# Arduino_Electronic_Load.net
KiCad netlist of a schematic drawn in EAGLE
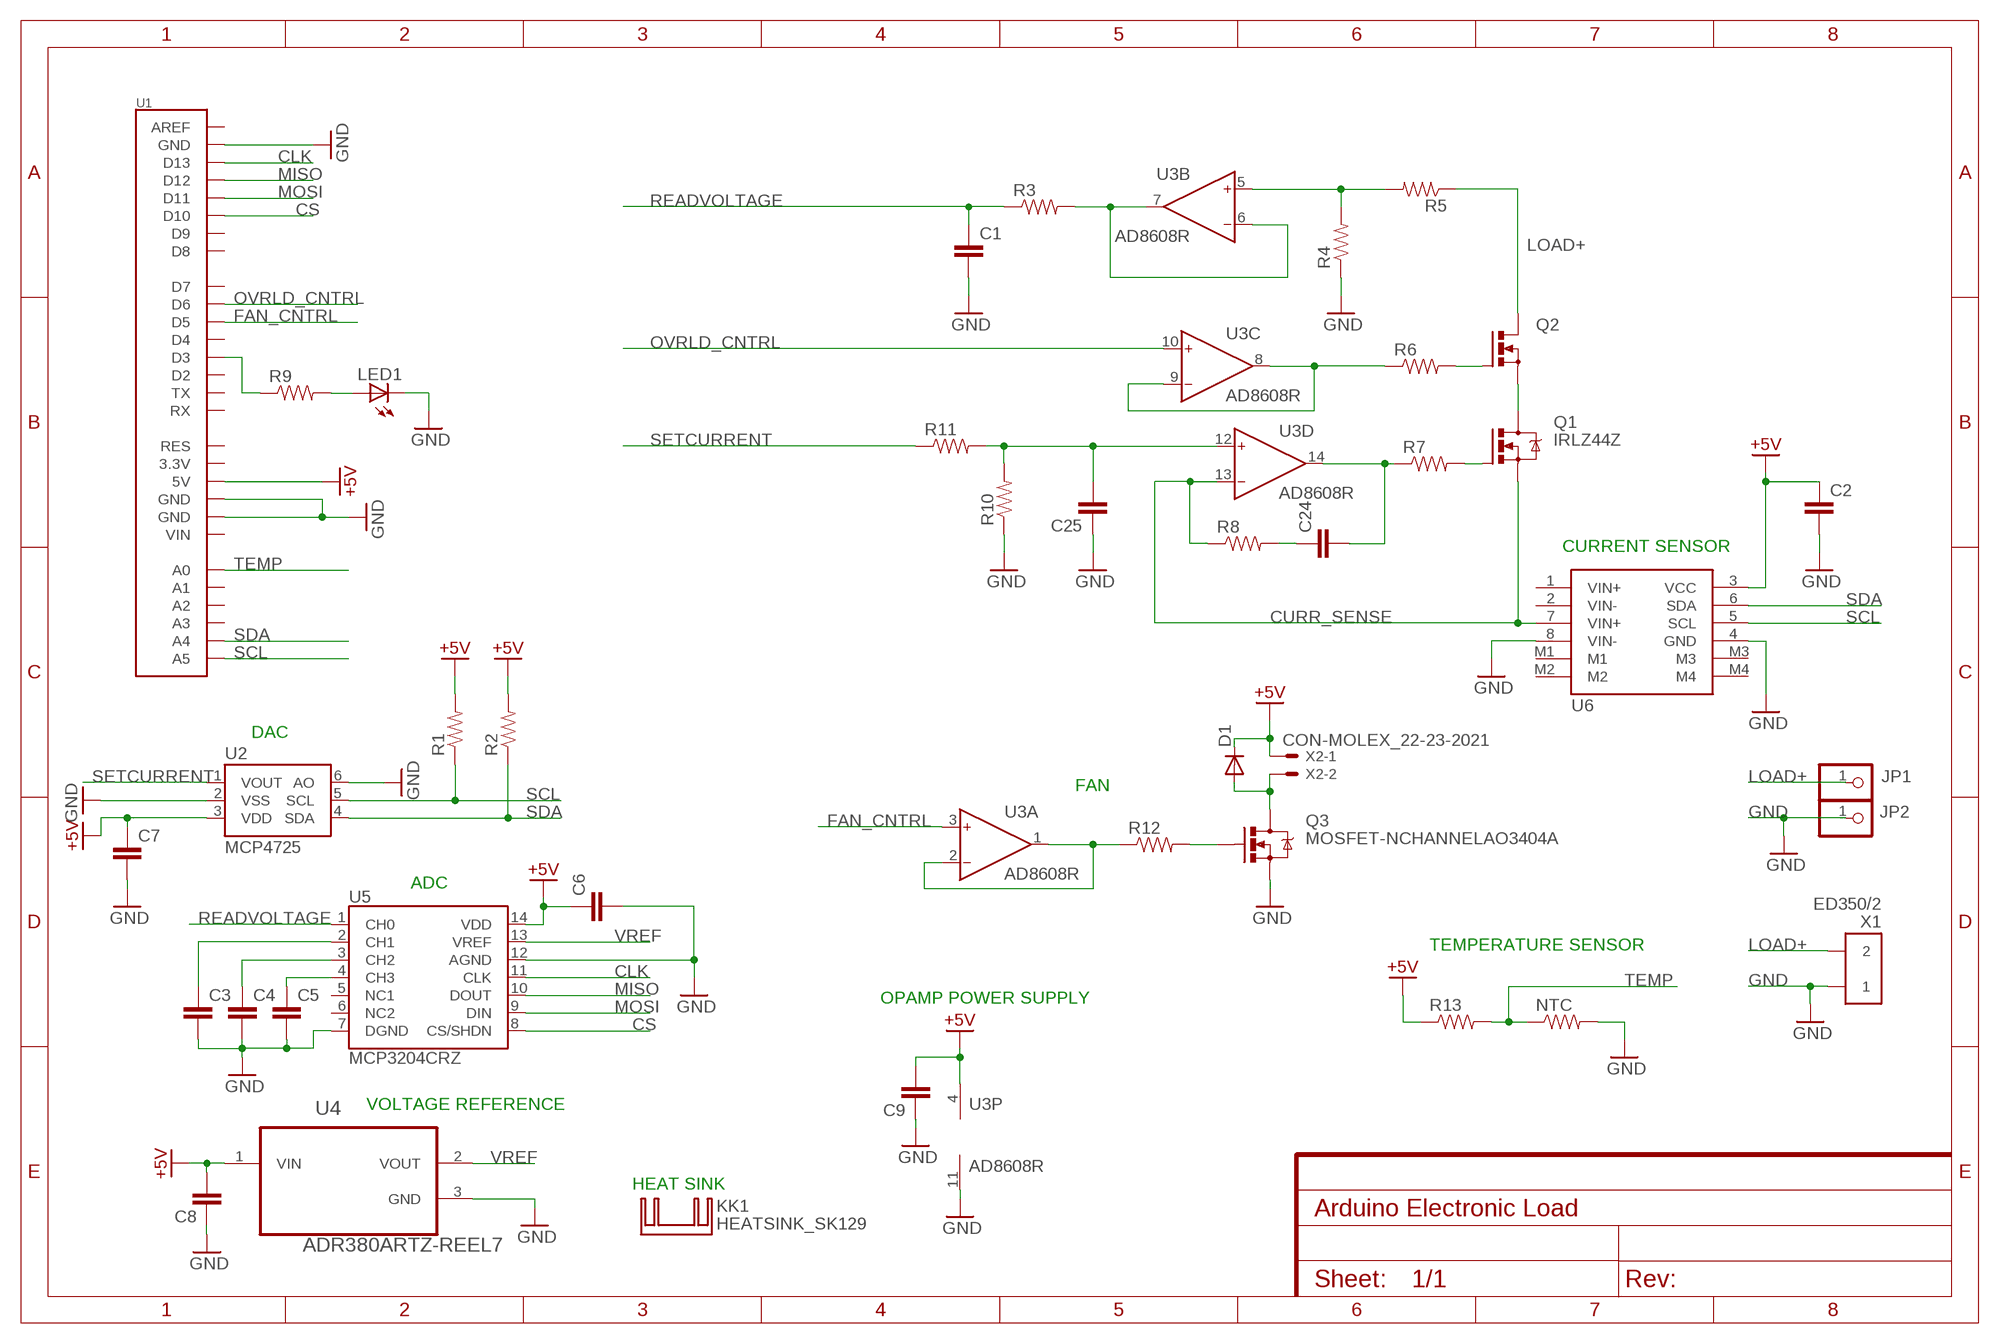
[diagram p0: schematic, sheet 1]

(export (version "E")
  (design (tool "Eeschema 10.0.6"))
  (components
    (comp (ref "C1")
      (value "CAP0603-CAP")
      (footprint "eagle-import:0603-CAP")
      (libsource (lib "eagle-import") (part "CAP0603-CAP"))
    )
    (comp (ref "C2")
      (value "CAP0603-CAP")
      (footprint "eagle-import:0603-CAP")
      (libsource (lib "eagle-import") (part "CAP0603-CAP"))
    )
    (comp (ref "C3")
      (value "CAP0603-CAP")
      (footprint "eagle-import:0603-CAP")
      (libsource (lib "eagle-import") (part "CAP0603-CAP"))
    )
    (comp (ref "C4")
      (value "CAP0603-CAP")
      (footprint "eagle-import:0603-CAP")
      (libsource (lib "eagle-import") (part "CAP0603-CAP"))
    )
    (comp (ref "C5")
      (value "CAP0603-CAP")
      (footprint "eagle-import:0603-CAP")
      (libsource (lib "eagle-import") (part "CAP0603-CAP"))
    )
    (comp (ref "C6")
      (value "CAP0603-CAP")
      (footprint "eagle-import:0603-CAP")
      (libsource (lib "eagle-import") (part "CAP0603-CAP"))
    )
    (comp (ref "C7")
      (value "CAP0603-CAP")
      (footprint "eagle-import:0603-CAP")
      (libsource (lib "eagle-import") (part "CAP0603-CAP"))
    )
    (comp (ref "C8")
      (value "CAP0603-CAP")
      (footprint "eagle-import:0603-CAP")
      (libsource (lib "eagle-import") (part "CAP0603-CAP"))
    )
    (comp (ref "C9")
      (value "CAP0603-CAP")
      (footprint "eagle-import:0603-CAP")
      (libsource (lib "eagle-import") (part "CAP0603-CAP"))
    )
    (comp (ref "C24")
      (value "CAP0603-CAP")
      (footprint "eagle-import:0603-CAP")
      (libsource (lib "eagle-import") (part "CAP0603-CAP"))
    )
    (comp (ref "C25")
      (value "CAP0603-CAP")
      (footprint "eagle-import:0603-CAP")
      (libsource (lib "eagle-import") (part "CAP0603-CAP"))
    )
    (comp (ref "D1")
      (value "DIODEPTH")
      (footprint "eagle-import:DIODE-1N4001")
      (libsource (lib "eagle-import") (part "DIODEPTH"))
    )
    (comp (ref "JP1")
      (value "PINHEAD_PINHD-1X1")
      (footprint "eagle-import:PINHEAD_1X01")
      (libsource (lib "eagle-import") (part "PINHEAD_PINHD-1X1"))
    )
    (comp (ref "JP2")
      (value "PINHEAD_PINHD-1X1")
      (footprint "eagle-import:PINHEAD_1X01")
      (libsource (lib "eagle-import") (part "PINHEAD_PINHD-1X1"))
    )
    (comp (ref "KK1")
      (value "HEATSINK_SK129")
      (footprint "eagle-import:HEATSINK_SK129-HOLE")
      (libsource (lib "eagle-import") (part "HEATSINK_SK129"))
    )
    (comp (ref "LED1")
      (value "LED5MM")
      (footprint "eagle-import:LED5MM")
      (libsource (lib "eagle-import") (part "LED5MM"))
    )
    (comp (ref "NTC")
      (value "RESISTOR0402-RES")
      (footprint "eagle-import:0402-RES")
      (libsource (lib "eagle-import") (part "RESISTOR0402-RES"))
    )
    (comp (ref "Q1")
      (value "IRLZ44Z")
      (footprint "eagle-import:TO220BV_1")
      (libsource (lib "eagle-import") (part "IRLZ44Z"))
    )
    (comp (ref "Q2")
      (value "PMOSFET_NTO220BV")
      (footprint "eagle-import:TO220BV")
      (libsource (lib "eagle-import") (part "PMOSFET_NTO220BV"))
    )
    (comp (ref "Q3")
      (value "MOSFET-NCHANNELAO3404A")
      (footprint "eagle-import:SOT23-3")
      (libsource (lib "eagle-import") (part "MOSFET-NCHANNELAO3404A"))
    )
    (comp (ref "R1")
      (value "RESISTOR0603-RES")
      (footprint "eagle-import:0603-RES")
      (libsource (lib "eagle-import") (part "RESISTOR0603-RES"))
    )
    (comp (ref "R2")
      (value "RESISTOR0603-RES")
      (footprint "eagle-import:0603-RES")
      (libsource (lib "eagle-import") (part "RESISTOR0603-RES"))
    )
    (comp (ref "R3")
      (value "RESISTOR0603-RES")
      (footprint "eagle-import:0603-RES")
      (libsource (lib "eagle-import") (part "RESISTOR0603-RES"))
    )
    (comp (ref "R4")
      (value "RESISTOR0603-RES")
      (footprint "eagle-import:0603-RES")
      (libsource (lib "eagle-import") (part "RESISTOR0603-RES"))
    )
    (comp (ref "R5")
      (value "RESISTOR0603-RES")
      (footprint "eagle-import:0603-RES")
      (libsource (lib "eagle-import") (part "RESISTOR0603-RES"))
    )
    (comp (ref "R6")
      (value "RESISTOR0603-RES")
      (footprint "eagle-import:0603-RES")
      (libsource (lib "eagle-import") (part "RESISTOR0603-RES"))
    )
    (comp (ref "R7")
      (value "RESISTOR0603-RES")
      (footprint "eagle-import:0603-RES")
      (libsource (lib "eagle-import") (part "RESISTOR0603-RES"))
    )
    (comp (ref "R8")
      (value "RESISTOR0603-RES")
      (footprint "eagle-import:0603-RES")
      (libsource (lib "eagle-import") (part "RESISTOR0603-RES"))
    )
    (comp (ref "R9")
      (value "RESISTOR0603-RES")
      (footprint "eagle-import:0603-RES")
      (libsource (lib "eagle-import") (part "RESISTOR0603-RES"))
    )
    (comp (ref "R10")
      (value "RESISTOR0603-RES")
      (footprint "eagle-import:0603-RES")
      (libsource (lib "eagle-import") (part "RESISTOR0603-RES"))
    )
    (comp (ref "R11")
      (value "RESISTOR0603-RES")
      (footprint "eagle-import:0603-RES")
      (libsource (lib "eagle-import") (part "RESISTOR0603-RES"))
    )
    (comp (ref "R12")
      (value "RESISTOR0603-RES")
      (footprint "eagle-import:0603-RES")
      (libsource (lib "eagle-import") (part "RESISTOR0603-RES"))
    )
    (comp (ref "R13")
      (value "RESISTOR0603-RES")
      (footprint "eagle-import:0603-RES")
      (libsource (lib "eagle-import") (part "RESISTOR0603-RES"))
    )
    (comp (ref "U1")
      (value "ARDUINO_SHIELD")
      (footprint "eagle-import:DUEMILANOVE_SHIELD")
      (libsource (lib "eagle-import") (part "ARDUINO_SHIELD"))
    )
    (comp (ref "U2")
      (value "MCP4725")
      (footprint "eagle-import:SOT23-6")
      (libsource (lib "eagle-import") (part "MCP4725SOT-23"))
    )
    (comp (ref "U3")
      (value "AD8608R")
      (footprint "eagle-import:SO14")
      (libsource (lib "eagle-import") (part "AD8608R"))
    )
    (comp (ref "U4")
      (value "ADR380ARTZ-REEL7")
      (footprint "eagle-import:SOT95P237X112-3N")
      (libsource (lib "eagle-import") (part "ADR380ARTZ-REEL7"))
    )
    (comp (ref "U5")
      (value "MCP3204CRZ")
      (footprint "eagle-import:SOIC-14")
      (libsource (lib "eagle-import") (part "MCP3204CRZ"))
    )
    (comp (ref "U6")
      (value "INA219")
      (footprint "eagle-import:INA219")
      (libsource (lib "eagle-import") (part "INA219"))
    )
    (comp (ref "X1")
      (value "ED350/2")
      (footprint "eagle-import:ED350_2")
      (libsource (lib "eagle-import") (part "ED350/2"))
    )
    (comp (ref "X2")
      (value "CON-MOLEX_22-23-2021")
      (footprint "eagle-import:CON-MOLEX_22-23-2021")
      (fields (field (name "MF") "MOLEX") (field (name "MPN") "22-23-2021"))
      (libsource (lib "eagle-import") (part "CON-MOLEX_22-23-2021"))
    )
  )
  (nets
    (net (code "1") (name "+5V") (class "Default")
      (node (ref "C2") (pin "1") (pinfunction "1_1") (pintype "passive"))
      (node (ref "C6") (pin "1") (pinfunction "1_1") (pintype "passive"))
      (node (ref "C7") (pin "1") (pinfunction "1_1") (pintype "passive"))
      (node (ref "C8") (pin "2") (pinfunction "2_2") (pintype "passive"))
      (node (ref "C9") (pin "2") (pinfunction "2_2") (pintype "passive"))
      (node (ref "D1") (pin "C") (pinfunction "C_C") (pintype "passive"))
      (node (ref "R1") (pin "2") (pinfunction "2_2") (pintype "passive"))
      (node (ref "R13") (pin "1") (pinfunction "1_1") (pintype "passive"))
      (node (ref "R2") (pin "2") (pinfunction "2_2") (pintype "passive"))
      (node (ref "U1") (pin "5V") (pinfunction "5V_5V") (pintype "bidirectional"))
      (node (ref "U2") (pin "3") (pinfunction "VDD_3") (pintype "bidirectional"))
      (node (ref "U3") (pin "4") (pinfunction "V+_4") (pintype "power_in"))
      (node (ref "U4") (pin "1") (pinfunction "VIN_1") (pintype "passive"))
      (node (ref "U5") (pin "14") (pinfunction "VDD_14") (pintype "bidirectional"))
      (node (ref "U6") (pin "3") (pinfunction "VCC_3") (pintype "bidirectional"))
      (node (ref "X2") (pin "1") (pinfunction "S_1") (pintype "passive"))
    )
    (net (code "2") (name "/CLK") (class "Default")
      (node (ref "U1") (pin "D13") (pinfunction "D13_D13") (pintype "bidirectional"))
      (node (ref "U5") (pin "11") (pinfunction "CLK_11") (pintype "bidirectional"))
    )
    (net (code "3") (name "/CS") (class "Default")
      (node (ref "U1") (pin "D10") (pinfunction "D10_D10") (pintype "bidirectional"))
      (node (ref "U5") (pin "8") (pinfunction "CS/SHDN_8") (pintype "bidirectional"))
    )
    (net (code "4") (name "/CURR_SENSE") (class "Default")
      (node (ref "Q1") (pin "S") (pinfunction "S_S") (pintype "passive"))
      (node (ref "R8") (pin "1") (pinfunction "1_1") (pintype "passive"))
      (node (ref "U3") (pin "13") (pinfunction "IN-_13") (pintype "input"))
      (node (ref "U6") (pin "7") (pinfunction "VIN+_7") (pintype "bidirectional"))
    )
    (net (code "5") (name "/FAN_CNTRL") (class "Default")
      (node (ref "U1") (pin "D5") (pinfunction "D5_D5") (pintype "bidirectional"))
      (node (ref "U3") (pin "3") (pinfunction "IN+_3") (pintype "input"))
    )
    (net (code "6") (name "/LOAD+") (class "Default")
      (node (ref "JP1") (pin "1") (pinfunction "1_1") (pintype "passive"))
      (node (ref "Q2") (pin "D") (pinfunction "D_D") (pintype "passive"))
      (node (ref "R5") (pin "1") (pinfunction "1_1") (pintype "passive"))
      (node (ref "X1") (pin "P$2") (pinfunction "2_P$2") (pintype "bidirectional"))
    )
    (net (code "7") (name "/MISO") (class "Default")
      (node (ref "U1") (pin "D12") (pinfunction "D12_D12") (pintype "bidirectional"))
      (node (ref "U5") (pin "10") (pinfunction "DOUT_10") (pintype "bidirectional"))
    )
    (net (code "8") (name "/MOSI") (class "Default")
      (node (ref "U1") (pin "D11") (pinfunction "D11_D11") (pintype "bidirectional"))
      (node (ref "U5") (pin "9") (pinfunction "DIN_9") (pintype "bidirectional"))
    )
    (net (code "9") (name "/OVRLD_CNTRL") (class "Default")
      (node (ref "U1") (pin "D6") (pinfunction "D6_D6") (pintype "bidirectional"))
      (node (ref "U3") (pin "10") (pinfunction "IN+_10") (pintype "input"))
    )
    (net (code "10") (name "/READVOLTAGE") (class "Default")
      (node (ref "C1") (pin "1") (pinfunction "1_1") (pintype "passive"))
      (node (ref "R3") (pin "1") (pinfunction "1_1") (pintype "passive"))
      (node (ref "U5") (pin "1") (pinfunction "CH0_1") (pintype "bidirectional"))
    )
    (net (code "11") (name "/SCL") (class "Default")
      (node (ref "R1") (pin "1") (pinfunction "1_1") (pintype "passive"))
      (node (ref "U1") (pin "A5") (pinfunction "A5_A5") (pintype "bidirectional"))
      (node (ref "U2") (pin "5") (pinfunction "SCL_5") (pintype "bidirectional"))
      (node (ref "U6") (pin "5") (pinfunction "SCL_5") (pintype "bidirectional"))
    )
    (net (code "12") (name "/SDA") (class "Default")
      (node (ref "R2") (pin "1") (pinfunction "1_1") (pintype "passive"))
      (node (ref "U1") (pin "A4") (pinfunction "A4_A4") (pintype "bidirectional"))
      (node (ref "U2") (pin "4") (pinfunction "SDA_4") (pintype "bidirectional"))
      (node (ref "U6") (pin "6") (pinfunction "SDA_6") (pintype "bidirectional"))
    )
    (net (code "13") (name "/SETCURRENT") (class "Default")
      (node (ref "R11") (pin "1") (pinfunction "1_1") (pintype "passive"))
      (node (ref "U2") (pin "1") (pinfunction "VOUT_1") (pintype "bidirectional"))
    )
    (net (code "14") (name "/TEMP") (class "Default")
      (node (ref "NTC") (pin "1") (pinfunction "1_1") (pintype "passive"))
      (node (ref "R13") (pin "2") (pinfunction "2_2") (pintype "passive"))
      (node (ref "U1") (pin "A0") (pinfunction "A0_A0") (pintype "bidirectional"))
    )
    (net (code "15") (name "/VREF") (class "Default")
      (node (ref "U4") (pin "2") (pinfunction "VOUT_2") (pintype "passive"))
      (node (ref "U5") (pin "13") (pinfunction "VREF_13") (pintype "bidirectional"))
    )
    (net (code "16") (name "GND") (class "Default")
      (node (ref "C1") (pin "2") (pinfunction "2_2") (pintype "passive"))
      (node (ref "C2") (pin "2") (pinfunction "2_2") (pintype "passive"))
      (node (ref "C25") (pin "1") (pinfunction "1_1") (pintype "passive"))
      (node (ref "C3") (pin "2") (pinfunction "2_2") (pintype "passive"))
      (node (ref "C4") (pin "2") (pinfunction "2_2") (pintype "passive"))
      (node (ref "C5") (pin "2") (pinfunction "2_2") (pintype "passive"))
      (node (ref "C6") (pin "2") (pinfunction "2_2") (pintype "passive"))
      (node (ref "C7") (pin "2") (pinfunction "2_2") (pintype "passive"))
      (node (ref "C8") (pin "1") (pinfunction "1_1") (pintype "passive"))
      (node (ref "C9") (pin "1") (pinfunction "1_1") (pintype "passive"))
      (node (ref "JP2") (pin "1") (pinfunction "1_1") (pintype "passive"))
      (node (ref "LED1") (pin "K") (pinfunction "C_K") (pintype "passive"))
      (node (ref "NTC") (pin "2") (pinfunction "2_2") (pintype "passive"))
      (node (ref "Q3") (pin "2") (pinfunction "S_2") (pintype "passive"))
      (node (ref "R10") (pin "1") (pinfunction "1_1") (pintype "passive"))
      (node (ref "R4") (pin "1") (pinfunction "1_1") (pintype "passive"))
      (node (ref "U1") (pin "GND@0") (pinfunction "GND_GND@0") (pintype "bidirectional"))
      (node (ref "U1") (pin "GND@1") (pinfunction "GND_GND@1") (pintype "bidirectional"))
      (node (ref "U1") (pin "GND@2") (pinfunction "GND_GND@2") (pintype "bidirectional"))
      (node (ref "U2") (pin "2") (pinfunction "VSS_2") (pintype "bidirectional"))
      (node (ref "U2") (pin "6") (pinfunction "AO_6") (pintype "bidirectional"))
      (node (ref "U3") (pin "11") (pinfunction "V-_11") (pintype "power_in"))
      (node (ref "U4") (pin "3") (pinfunction "GND_3") (pintype "passive"))
      (node (ref "U5") (pin "12") (pinfunction "AGND_12") (pintype "bidirectional"))
      (node (ref "U5") (pin "7") (pinfunction "DGND_7") (pintype "bidirectional"))
      (node (ref "U6") (pin "4") (pinfunction "GND_4") (pintype "bidirectional"))
      (node (ref "U6") (pin "8") (pinfunction "VIN-_8") (pintype "bidirectional"))
      (node (ref "X1") (pin "P$1") (pinfunction "1_P$1") (pintype "bidirectional"))
    )
    (net (code "17") (name "Net-(C24-Pad1)") (class "Default")
      (node (ref "C24") (pin "1") (pinfunction "1_1") (pintype "passive"))
      (node (ref "R8") (pin "2") (pinfunction "2_2") (pintype "passive"))
    )
    (net (code "18") (name "Net-(LED1-PadA)") (class "Default")
      (node (ref "LED1") (pin "A") (pinfunction "A_A") (pintype "passive"))
      (node (ref "R9") (pin "2") (pinfunction "2_2") (pintype "passive"))
    )
    (net (code "19") (name "Net-(Q1-PadD)") (class "Default")
      (node (ref "Q1") (pin "D") (pinfunction "D_D") (pintype "passive"))
      (node (ref "Q2") (pin "S") (pinfunction "S_S") (pintype "passive"))
    )
    (net (code "20") (name "Net-(Q1-PadG)") (class "Default")
      (node (ref "Q1") (pin "G") (pinfunction "G_G") (pintype "passive"))
      (node (ref "R7") (pin "2") (pinfunction "2_2") (pintype "passive"))
    )
    (net (code "21") (name "Net-(Q2-PadG)") (class "Default")
      (node (ref "Q2") (pin "G") (pinfunction "G_G") (pintype "passive"))
      (node (ref "R6") (pin "2") (pinfunction "2_2") (pintype "passive"))
    )
    (net (code "22") (name "Net-(Q3-D)") (class "Default")
      (node (ref "D1") (pin "A") (pinfunction "A_A") (pintype "passive"))
      (node (ref "Q3") (pin "3") (pinfunction "D_3") (pintype "passive"))
      (node (ref "X2") (pin "2") (pinfunction "S_2") (pintype "passive"))
    )
    (net (code "23") (name "Net-(Q3-G)") (class "Default")
      (node (ref "Q3") (pin "1") (pinfunction "G_1") (pintype "passive"))
      (node (ref "R12") (pin "2") (pinfunction "2_2") (pintype "passive"))
    )
    (net (code "24") (name "Net-(R9-Pad1)") (class "Default")
      (node (ref "R9") (pin "1") (pinfunction "1_1") (pintype "passive"))
      (node (ref "U1") (pin "D3") (pinfunction "D3_D3") (pintype "bidirectional"))
    )
    (net (code "25") (name "Net-(U3A-IN-)") (class "Default")
      (node (ref "R12") (pin "1") (pinfunction "1_1") (pintype "passive"))
      (node (ref "U3") (pin "1") (pinfunction "OUT_1") (pintype "output"))
      (node (ref "U3") (pin "2") (pinfunction "IN-_2") (pintype "input"))
    )
    (net (code "26") (name "Net-(U3B-IN+)") (class "Default")
      (node (ref "R4") (pin "2") (pinfunction "2_2") (pintype "passive"))
      (node (ref "R5") (pin "2") (pinfunction "2_2") (pintype "passive"))
      (node (ref "U3") (pin "5") (pinfunction "IN+_5") (pintype "input"))
    )
    (net (code "27") (name "Net-(U3B-IN-)") (class "Default")
      (node (ref "R3") (pin "2") (pinfunction "2_2") (pintype "passive"))
      (node (ref "U3") (pin "6") (pinfunction "IN-_6") (pintype "input"))
      (node (ref "U3") (pin "7") (pinfunction "OUT_7") (pintype "output"))
    )
    (net (code "28") (name "Net-(U3C-IN-)") (class "Default")
      (node (ref "R6") (pin "1") (pinfunction "1_1") (pintype "passive"))
      (node (ref "U3") (pin "8") (pinfunction "OUT_8") (pintype "output"))
      (node (ref "U3") (pin "9") (pinfunction "IN-_9") (pintype "input"))
    )
    (net (code "29") (name "Net-(U3D-IN+)") (class "Default")
      (node (ref "C25") (pin "2") (pinfunction "2_2") (pintype "passive"))
      (node (ref "R10") (pin "2") (pinfunction "2_2") (pintype "passive"))
      (node (ref "R11") (pin "2") (pinfunction "2_2") (pintype "passive"))
      (node (ref "U3") (pin "12") (pinfunction "IN+_12") (pintype "input"))
    )
    (net (code "30") (name "Net-(U3D-OUT)") (class "Default")
      (node (ref "C24") (pin "2") (pinfunction "2_2") (pintype "passive"))
      (node (ref "R7") (pin "1") (pinfunction "1_1") (pintype "passive"))
      (node (ref "U3") (pin "14") (pinfunction "OUT_14") (pintype "output"))
    )
    (net (code "31") (name "Net-(U5-CH1)") (class "Default")
      (node (ref "C3") (pin "1") (pinfunction "1_1") (pintype "passive"))
      (node (ref "U5") (pin "2") (pinfunction "CH1_2") (pintype "bidirectional"))
    )
    (net (code "32") (name "Net-(U5-CH2)") (class "Default")
      (node (ref "C4") (pin "1") (pinfunction "1_1") (pintype "passive"))
      (node (ref "U5") (pin "3") (pinfunction "CH2_3") (pintype "bidirectional"))
    )
    (net (code "33") (name "Net-(U5-CH3)") (class "Default")
      (node (ref "C5") (pin "1") (pinfunction "1_1") (pintype "passive"))
      (node (ref "U5") (pin "4") (pinfunction "CH3_4") (pintype "bidirectional"))
    )
    (net (code "34") (name "unconnected-(U1-Pad3.3V)") (class "Default")
      (node (ref "U1") (pin "3.3V") (pinfunction "3.3V_3.3V") (pintype "bidirectional"))
    )
    (net (code "35") (name "unconnected-(U1-PadA1)") (class "Default")
      (node (ref "U1") (pin "A1") (pinfunction "A1_A1") (pintype "bidirectional"))
    )
    (net (code "36") (name "unconnected-(U1-PadA2)") (class "Default")
      (node (ref "U1") (pin "A2") (pinfunction "A2_A2") (pintype "bidirectional"))
    )
    (net (code "37") (name "unconnected-(U1-PadA3)") (class "Default")
      (node (ref "U1") (pin "A3") (pinfunction "A3_A3") (pintype "bidirectional"))
    )
    (net (code "38") (name "unconnected-(U1-PadAREF)") (class "Default")
      (node (ref "U1") (pin "AREF") (pinfunction "AREF_AREF") (pintype "bidirectional"))
    )
    (net (code "39") (name "unconnected-(U1-PadD2)") (class "Default")
      (node (ref "U1") (pin "D2") (pinfunction "D2_D2") (pintype "bidirectional"))
    )
    (net (code "40") (name "unconnected-(U1-PadD4)") (class "Default")
      (node (ref "U1") (pin "D4") (pinfunction "D4_D4") (pintype "bidirectional"))
    )
    (net (code "41") (name "unconnected-(U1-PadD7)") (class "Default")
      (node (ref "U1") (pin "D7") (pinfunction "D7_D7") (pintype "bidirectional"))
    )
    (net (code "42") (name "unconnected-(U1-PadD8)") (class "Default")
      (node (ref "U1") (pin "D8") (pinfunction "D8_D8") (pintype "bidirectional"))
    )
    (net (code "43") (name "unconnected-(U1-PadD9)") (class "Default")
      (node (ref "U1") (pin "D9") (pinfunction "D9_D9") (pintype "bidirectional"))
    )
    (net (code "44") (name "unconnected-(U1-PadRES)") (class "Default")
      (node (ref "U1") (pin "RES") (pinfunction "RES_RES") (pintype "bidirectional"))
    )
    (net (code "45") (name "unconnected-(U1-PadRX)") (class "Default")
      (node (ref "U1") (pin "RX") (pinfunction "RX_RX") (pintype "bidirectional"))
    )
    (net (code "46") (name "unconnected-(U1-PadTX)") (class "Default")
      (node (ref "U1") (pin "TX") (pinfunction "TX_TX") (pintype "bidirectional"))
    )
    (net (code "47") (name "unconnected-(U1-PadVIN)") (class "Default")
      (node (ref "U1") (pin "VIN") (pinfunction "VIN_VIN") (pintype "bidirectional"))
    )
    (net (code "48") (name "unconnected-(U5-NC1-Pad5)") (class "Default")
      (node (ref "U5") (pin "5") (pinfunction "NC1_5") (pintype "bidirectional"))
    )
    (net (code "49") (name "unconnected-(U5-NC2-Pad6)") (class "Default")
      (node (ref "U5") (pin "6") (pinfunction "NC2_6") (pintype "bidirectional"))
    )
    (net (code "50") (name "unconnected-(U6-PadM1)") (class "Default")
      (node (ref "U6") (pin "M1") (pinfunction "M1_M1") (pintype "bidirectional"))
    )
    (net (code "51") (name "unconnected-(U6-PadM2)") (class "Default")
      (node (ref "U6") (pin "M2") (pinfunction "M2_M2") (pintype "bidirectional"))
    )
    (net (code "52") (name "unconnected-(U6-PadM3)") (class "Default")
      (node (ref "U6") (pin "M3") (pinfunction "M3_M3") (pintype "bidirectional"))
    )
    (net (code "53") (name "unconnected-(U6-PadM4)") (class "Default")
      (node (ref "U6") (pin "M4") (pinfunction "M4_M4") (pintype "bidirectional"))
    )
    (net (code "54") (name "unconnected-(U6-VIN+-Pad1)") (class "Default")
      (node (ref "U6") (pin "1") (pinfunction "VIN+_1") (pintype "bidirectional"))
    )
    (net (code "55") (name "unconnected-(U6-VIN--Pad2)") (class "Default")
      (node (ref "U6") (pin "2") (pinfunction "VIN-_2") (pintype "bidirectional"))
    )
  )
)
